# Sheet_1.net
KiCad netlist of a schematic drawn in Altium Designer
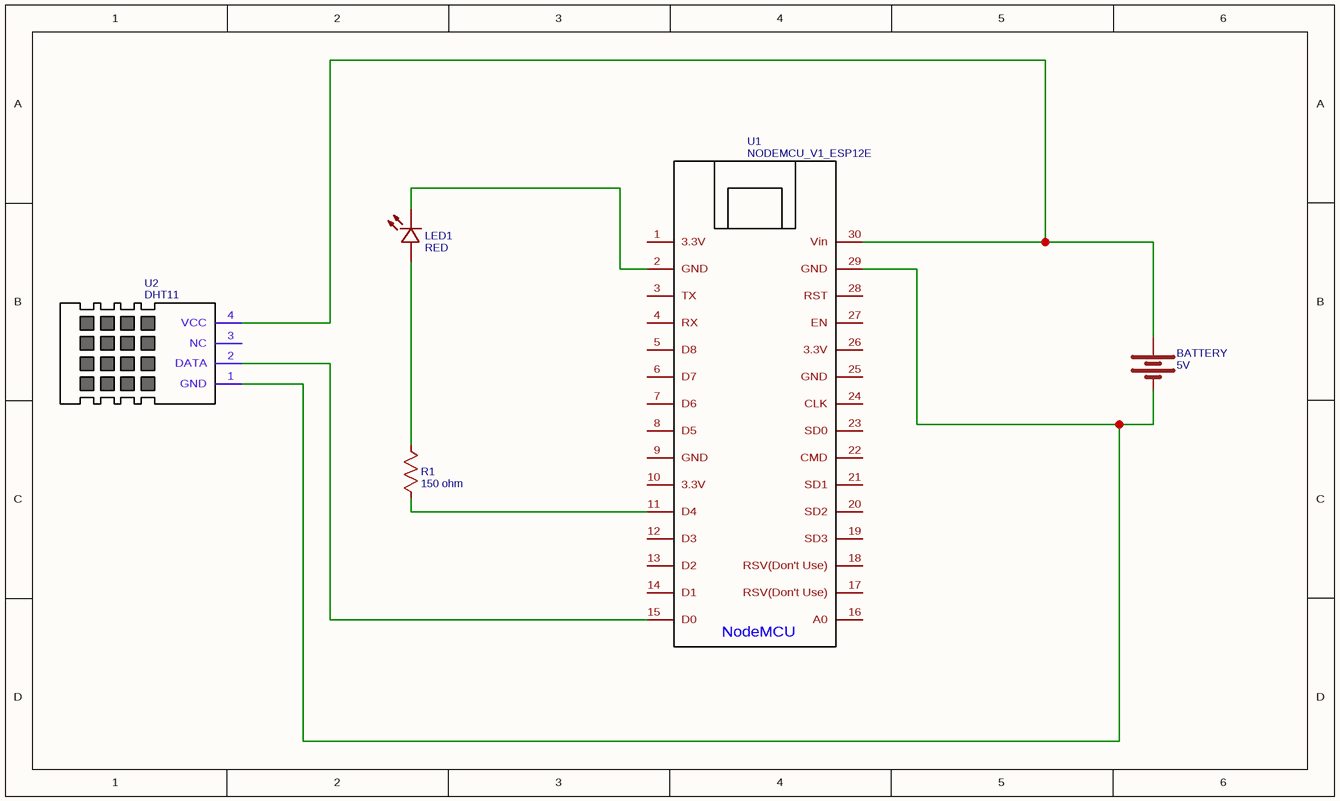
[diagram p0: Sheet_1.schdoc]

(export (version "E")
  (design (tool "Eeschema 10.0.6"))
  (components
    (comp (ref "5V")
      (value "BATTERY")
      (fields (field (name "CONTRIBUTOR") "SparkFun"))
      (libsource (lib "altium-import") (part "root_1_BATTERY_"))
    )
    (comp (ref "LED1")
      (value "RED")
      (fields
        (field (name "BOM_MANUFACTURER PART") "204-10SURD/S530-A3")
        (field (name "BOM_SUPPLIER PART") "C99772")
      )
      (libsource (lib "altium-import") (part "root_1_RED_"))
    )
    (comp (ref "R1") (value "150 ohm") (libsource (lib "altium-import") (part "root_3_150 ohm_")))
    (comp (ref "U1")
      (value "NODEMCU_V1_ESP12E")
      (fields (field (name "CONTRIBUTOR") "jhro1004"))
      (libsource (lib "altium-import") (part "root_0_NODEMCU_V1_ESP12E_"))
    )
    (comp (ref "U2")
      (value "DHT11")
      (fields (field (name "BOM_SUPPLIER PART") "PRODUCT ID: 385"))
      (libsource (lib "altium-import") (part "root_1_DHT11_"))
    )
  )
  (nets
    (net (code "1") (name "Net-(5V-+)") (class "Default")
      (node (ref "5V") (pin "PWR@1") (pinfunction "+_PWR@1") (pintype "passive"))
      (node (ref "U1") (pin "30") (pinfunction "Vin_30") (pintype "passive"))
      (node (ref "U2") (pin "4") (pinfunction "VCC_4") (pintype "passive"))
    )
    (net (code "2") (name "Net-(5V--)") (class "Default")
      (node (ref "5V") (pin "GND@1") (pinfunction "-_GND@1") (pintype "passive"))
      (node (ref "U1") (pin "29") (pinfunction "GND_29") (pintype "passive"))
      (node (ref "U2") (pin "1") (pinfunction "GND_1") (pintype "passive"))
    )
    (net (code "3") (name "Net-(LED1-A)") (class "Default")
      (node (ref "LED1") (pin "1") (pinfunction "A_1") (pintype "passive"))
      (node (ref "R1") (pin "1") (pinfunction "1_1") (pintype "passive"))
    )
    (net (code "4") (name "Net-(LED1-K)") (class "Default")
      (node (ref "LED1") (pin "2") (pinfunction "K_2") (pintype "passive"))
      (node (ref "U1") (pin "2") (pinfunction "GND_2") (pintype "passive"))
    )
    (net (code "5") (name "Net-(U1-D0)") (class "Default")
      (node (ref "U1") (pin "15") (pinfunction "D0_15") (pintype "passive"))
      (node (ref "U2") (pin "2") (pinfunction "DATA_2") (pintype "passive"))
    )
    (net (code "6") (name "Net-(U1-D4)") (class "Default")
      (node (ref "R1") (pin "2") (pinfunction "2_2") (pintype "passive"))
      (node (ref "U1") (pin "11") (pinfunction "D4_11") (pintype "passive"))
    )
    (net (code "7") (name "unconnected-(U1-3.3V-Pad1)") (class "Default")
      (node (ref "U1") (pin "1") (pinfunction "3.3V_1") (pintype "passive"))
    )
    (net (code "8") (name "unconnected-(U1-3.3V-Pad10)") (class "Default")
      (node (ref "U1") (pin "10") (pinfunction "3.3V_10") (pintype "passive"))
    )
    (net (code "9") (name "unconnected-(U1-3.3V-Pad26)") (class "Default")
      (node (ref "U1") (pin "26") (pinfunction "3.3V_26") (pintype "passive"))
    )
    (net (code "10") (name "unconnected-(U1-A0-Pad16)") (class "Default")
      (node (ref "U1") (pin "16") (pinfunction "A0_16") (pintype "passive"))
    )
    (net (code "11") (name "unconnected-(U1-CLK-Pad24)") (class "Default")
      (node (ref "U1") (pin "24") (pinfunction "CLK_24") (pintype "passive"))
    )
    (net (code "12") (name "unconnected-(U1-CMD-Pad22)") (class "Default")
      (node (ref "U1") (pin "22") (pinfunction "CMD_22") (pintype "passive"))
    )
    (net (code "13") (name "unconnected-(U1-D1-Pad14)") (class "Default")
      (node (ref "U1") (pin "14") (pinfunction "D1_14") (pintype "passive"))
    )
    (net (code "14") (name "unconnected-(U1-D2-Pad13)") (class "Default")
      (node (ref "U1") (pin "13") (pinfunction "D2_13") (pintype "passive"))
    )
    (net (code "15") (name "unconnected-(U1-D3-Pad12)") (class "Default")
      (node (ref "U1") (pin "12") (pinfunction "D3_12") (pintype "passive"))
    )
    (net (code "16") (name "unconnected-(U1-D5-Pad8)") (class "Default")
      (node (ref "U1") (pin "8") (pinfunction "D5_8") (pintype "passive"))
    )
    (net (code "17") (name "unconnected-(U1-D6-Pad7)") (class "Default")
      (node (ref "U1") (pin "7") (pinfunction "D6_7") (pintype "passive"))
    )
    (net (code "18") (name "unconnected-(U1-D7-Pad6)") (class "Default")
      (node (ref "U1") (pin "6") (pinfunction "D7_6") (pintype "passive"))
    )
    (net (code "19") (name "unconnected-(U1-D8-Pad5)") (class "Default")
      (node (ref "U1") (pin "5") (pinfunction "D8_5") (pintype "passive"))
    )
    (net (code "20") (name "unconnected-(U1-EN-Pad27)") (class "Default")
      (node (ref "U1") (pin "27") (pinfunction "EN_27") (pintype "passive"))
    )
    (net (code "21") (name "unconnected-(U1-GND-Pad9)") (class "Default")
      (node (ref "U1") (pin "9") (pinfunction "GND_9") (pintype "passive"))
    )
    (net (code "22") (name "unconnected-(U1-GND-Pad25)") (class "Default")
      (node (ref "U1") (pin "25") (pinfunction "GND_25") (pintype "passive"))
    )
    (net (code "23") (name "unconnected-(U1-RST-Pad28)") (class "Default")
      (node (ref "U1") (pin "28") (pinfunction "RST_28") (pintype "passive"))
    )
    (net (code "24") (name "unconnected-(U1-RSV(Don't_Use)-Pad17)") (class "Default")
      (node (ref "U1") (pin "17") (pinfunction "RSV(Don't_Use)_17") (pintype "passive"))
    )
    (net (code "25") (name "unconnected-(U1-RSV(Don't_Use)-Pad18)") (class "Default")
      (node (ref "U1") (pin "18") (pinfunction "RSV(Don't_Use)_18") (pintype "passive"))
    )
    (net (code "26") (name "unconnected-(U1-RX-Pad4)") (class "Default")
      (node (ref "U1") (pin "4") (pinfunction "RX_4") (pintype "passive"))
    )
    (net (code "27") (name "unconnected-(U1-SD0-Pad23)") (class "Default")
      (node (ref "U1") (pin "23") (pinfunction "SD0_23") (pintype "passive"))
    )
    (net (code "28") (name "unconnected-(U1-SD1-Pad21)") (class "Default")
      (node (ref "U1") (pin "21") (pinfunction "SD1_21") (pintype "passive"))
    )
    (net (code "29") (name "unconnected-(U1-SD2-Pad20)") (class "Default")
      (node (ref "U1") (pin "20") (pinfunction "SD2_20") (pintype "passive"))
    )
    (net (code "30") (name "unconnected-(U1-SD3-Pad19)") (class "Default")
      (node (ref "U1") (pin "19") (pinfunction "SD3_19") (pintype "passive"))
    )
    (net (code "31") (name "unconnected-(U1-TX-Pad3)") (class "Default")
      (node (ref "U1") (pin "3") (pinfunction "TX_3") (pintype "passive"))
    )
    (net (code "32") (name "unconnected-(U2-NC-Pad3)") (class "Default")
      (node (ref "U2") (pin "3") (pinfunction "NC_3") (pintype "passive"))
    )
  )
)
